# ConstantCurrentTester.net
KiCad netlist of a schematic drawn in EAGLE
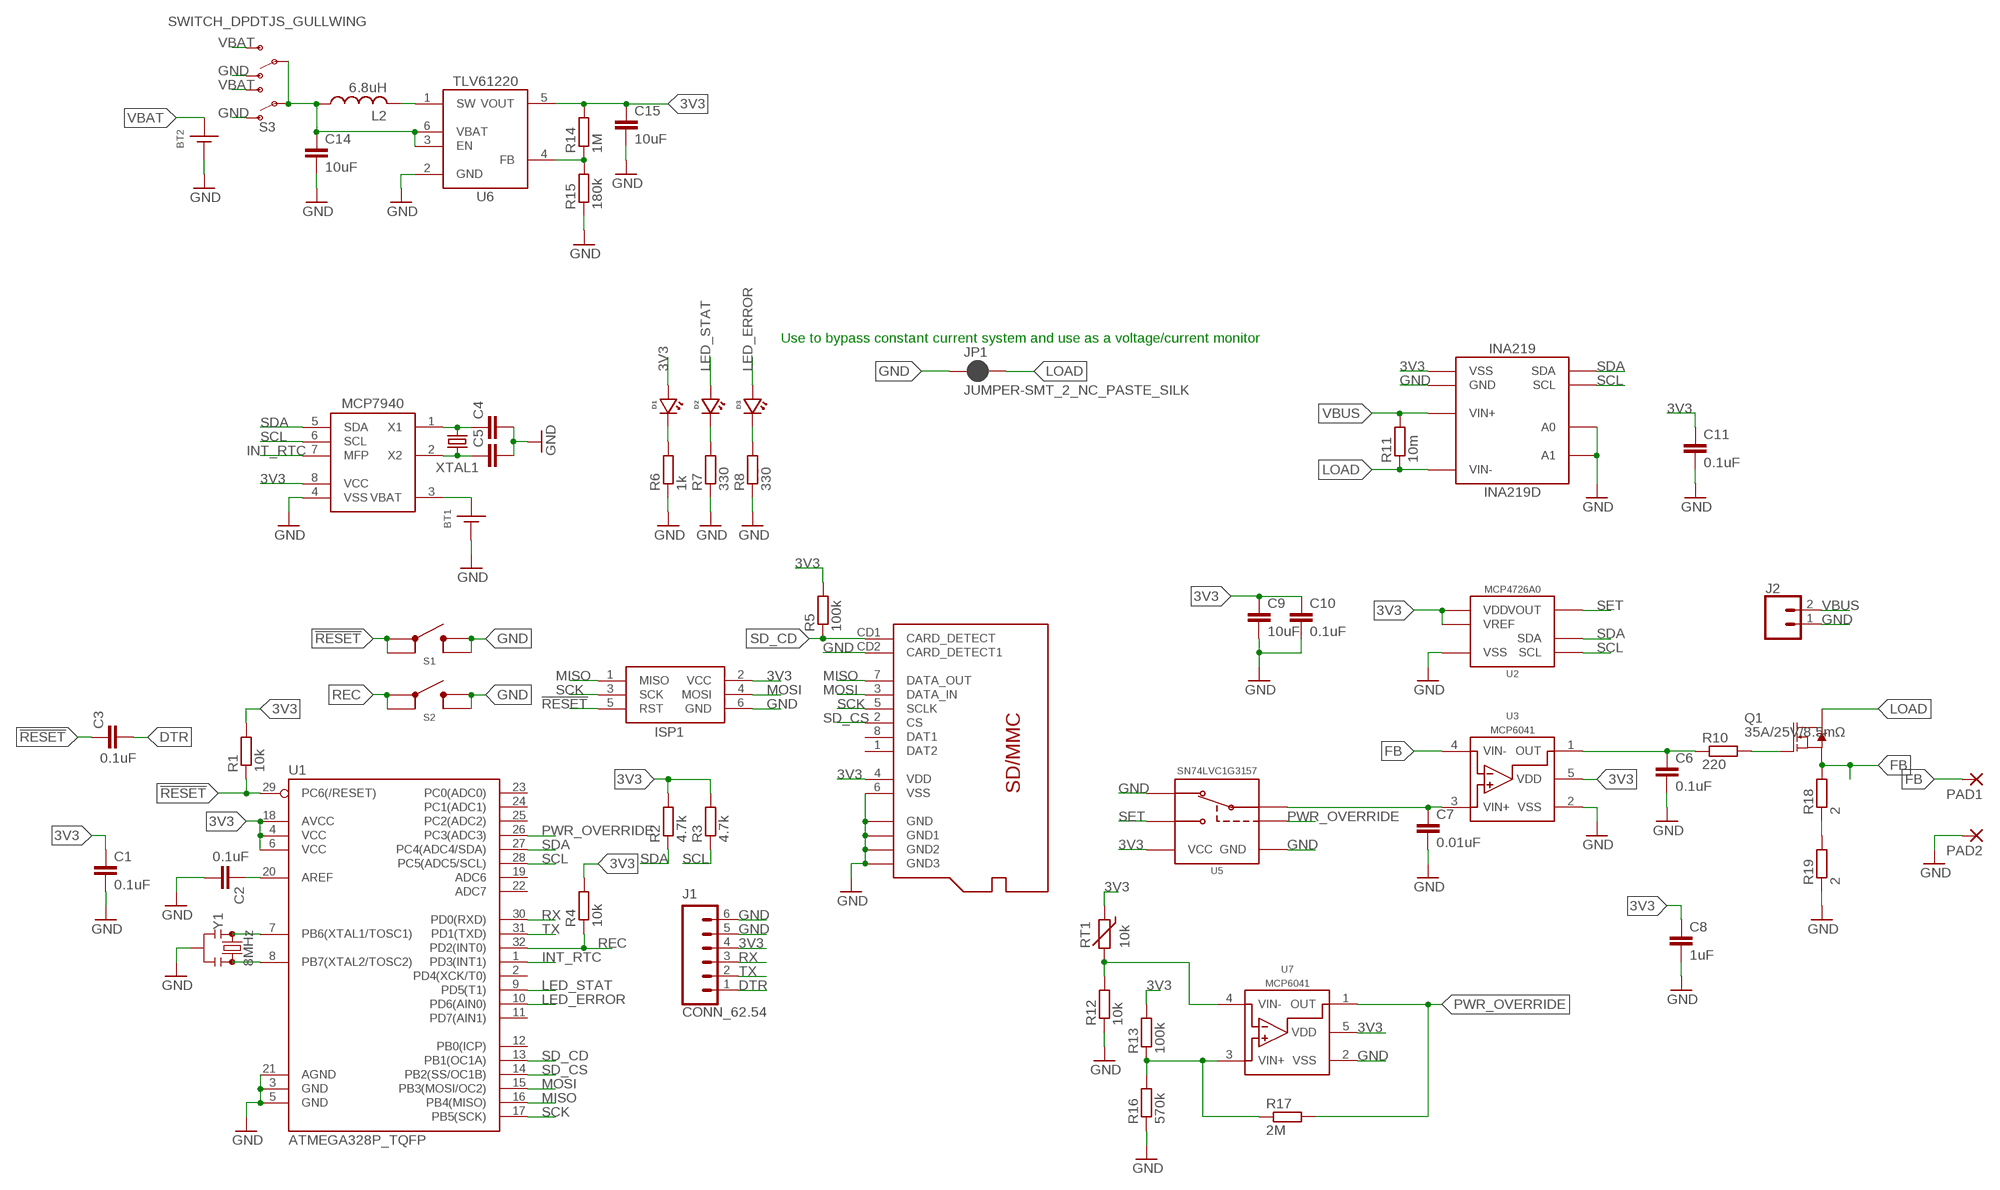
[diagram p0: schematic, sheet 1]

(export (version "E")
  (design (tool "Eeschema 10.0.6"))
  (components
    (comp (ref "BT1")
      (value "BATTERY_COIN12MM")
      (footprint "eagle-import:LINX_BAT-HLD-012-SMT")
      (fields (field (name "MF") "Linx") (field (name "MPN") "BAT-HLD-012-SMT"))
      (libsource (lib "eagle-import") (part "BATTERY_COIN12MM"))
    )
    (comp (ref "BT2")
      (value "BATTERY_COINAA")
      (footprint "eagle-import:BK-53")
      (libsource (lib "eagle-import") (part "BATTERY_COINAA"))
    )
    (comp (ref "C1")
      (value "0.1uF")
      (footprint "eagle-import:C0603")
      (fields (field (name "MF") "Murata") (field (name "MPN") "GCM188R71E104KA57D"))
      (libsource (lib "eagle-import") (part "C-EUC06030.1UF"))
    )
    (comp (ref "C2")
      (value "0.1uF")
      (footprint "eagle-import:C0603")
      (fields (field (name "MF") "Murata") (field (name "MPN") "GCM188R71E104KA57D"))
      (libsource (lib "eagle-import") (part "C-EUC06030.1UF"))
    )
    (comp (ref "C3")
      (value "0.1uF")
      (footprint "eagle-import:C0603")
      (fields (field (name "MF") "Murata") (field (name "MPN") "GCM188R71E104KA57D"))
      (libsource (lib "eagle-import") (part "C-EUC06030.1UF"))
    )
    (comp (ref "C4")
      (value "C-EUC0603")
      (footprint "eagle-import:C0603")
      (libsource (lib "eagle-import") (part "C-EUC0603"))
    )
    (comp (ref "C5")
      (value "C-EUC0603")
      (footprint "eagle-import:C0603")
      (libsource (lib "eagle-import") (part "C-EUC0603"))
    )
    (comp (ref "C6")
      (value "0.1uF")
      (footprint "eagle-import:C0603")
      (fields (field (name "MF") "Murata") (field (name "MPN") "GCM188R71E104KA57D"))
      (libsource (lib "eagle-import") (part "C-EUC06030.1UF"))
    )
    (comp (ref "C7")
      (value "0.01uF")
      (footprint "eagle-import:C0603")
      (libsource (lib "eagle-import") (part "C-EUC0603"))
    )
    (comp (ref "C8")
      (value "1uF")
      (footprint "eagle-import:C0603")
      (fields (field (name "MF") "Yaiyo Yuden") (field (name "MPN") "EMK107BJ105KA-T"))
      (libsource (lib "eagle-import") (part "C-EUC06031UF"))
    )
    (comp (ref "C9")
      (value "10uF")
      (footprint "eagle-import:C0805")
      (fields (field (name "MF") "Murata") (field (name "MPN") "GRM21BR61C106KE15K"))
      (libsource (lib "eagle-import") (part "C-EUC080510UF"))
    )
    (comp (ref "C10")
      (value "0.1uF")
      (footprint "eagle-import:C0603")
      (fields (field (name "MF") "Murata") (field (name "MPN") "GCM188R71E104KA57D"))
      (libsource (lib "eagle-import") (part "C-EUC06030.1UF"))
    )
    (comp (ref "C11")
      (value "0.1uF")
      (footprint "eagle-import:C0603")
      (fields (field (name "MF") "Murata") (field (name "MPN") "GCM188R71E104KA57D"))
      (libsource (lib "eagle-import") (part "C-EUC06030.1UF"))
    )
    (comp (ref "C14")
      (value "10uF")
      (footprint "eagle-import:C0805")
      (fields (field (name "MF") "Murata") (field (name "MPN") "GRM21BR61C106KE15K"))
      (libsource (lib "eagle-import") (part "C-EUC080510UF"))
    )
    (comp (ref "C15")
      (value "10uF")
      (footprint "eagle-import:C0805")
      (fields (field (name "MF") "Murata") (field (name "MPN") "GRM21BR61C106KE15K"))
      (libsource (lib "eagle-import") (part "C-EUC080510UF"))
    )
    (comp (ref "D1")
      (value "LEDBLUE0603")
      (footprint "eagle-import:LED_0603")
      (fields (field (name "MF") "Wurth") (field (name "MPN") "150060BS75000"))
      (libsource (lib "eagle-import") (part "LED0603BLUE"))
    )
    (comp (ref "D2")
      (value "LEDGREEN0603")
      (footprint "eagle-import:LED_0603")
      (fields (field (name "MF") "Wurth") (field (name "MPN") "150060GS75000"))
      (libsource (lib "eagle-import") (part "LED0603GREEN"))
    )
    (comp (ref "D3")
      (value "LEDRED0603")
      (footprint "eagle-import:LED_0603")
      (fields (field (name "MF") "Wurth") (field (name "MPN") "150060RS75000"))
      (libsource (lib "eagle-import") (part "LED0603RED"))
    )
    (comp (ref "ISP1")
      (value "AVRISP-6")
      (footprint "eagle-import:AVRISP")
      (libsource (lib "eagle-import") (part "AVRISP-6"))
    )
    (comp (ref "J1")
      (value "CONN_62.54")
      (footprint "eagle-import:1X06")
      (libsource (lib "eagle-import") (part "CONN_62.54"))
    )
    (comp (ref "J2")
      (value "CONN_023.5MM")
      (footprint "eagle-import:SCREWTERMINAL-3.5MM-2")
      (fields (field (name "MF") "On Shore Technology") (field (name "MPN") "OSTTE020161"))
      (libsource (lib "eagle-import") (part "CONN_023.5MM"))
    )
    (comp (ref "JP1")
      (value "JUMPER-SMT_2_NC_PASTE_SILK")
      (footprint "eagle-import:SMT-JUMPER_2_NC_PASTE_SILK")
      (libsource (lib "eagle-import") (part "JUMPER-SMT_2_NC_PASTE_SILK"))
    )
    (comp (ref "L2")
      (value "6.8uH")
      (footprint "eagle-import:1008")
      (fields (field (name "MF") "Wurth") (field (name "MPN") "74438323068"))
      (libsource (lib "eagle-import") (part "INDUCTOR1008"))
    )
    (comp (ref "PAD1")
      (value "3,81/1,4")
      (footprint "eagle-import:3,81_1,4")
      (libsource (lib "eagle-import") (part "3,81/1,4"))
    )
    (comp (ref "PAD2")
      (value "3,81/1,4")
      (footprint "eagle-import:3,81_1,4")
      (libsource (lib "eagle-import") (part "3,81/1,4"))
    )
    (comp (ref "Q1")
      (value "35A/25V/8.5mΩ")
      (footprint "eagle-import:DPAK")
      (libsource (lib "eagle-import") (part "MOSFET-NCH-FDD8780"))
    )
    (comp (ref "R1")
      (value "10k")
      (footprint "eagle-import:R0603")
      (fields (field (name "MF") "Yageo") (field (name "MPN") "RC0603FR-0710KL"))
      (libsource (lib "eagle-import") (part "R-EU_R060310K"))
    )
    (comp (ref "R2")
      (value "4.7k")
      (footprint "eagle-import:R0603")
      (fields (field (name "MF") "Yageo") (field (name "MPN") "RC0603FR-074K7L"))
      (libsource (lib "eagle-import") (part "R-EU_R06034.7K"))
    )
    (comp (ref "R3")
      (value "4.7k")
      (footprint "eagle-import:R0603")
      (fields (field (name "MF") "Yageo") (field (name "MPN") "RC0603FR-074K7L"))
      (libsource (lib "eagle-import") (part "R-EU_R06034.7K"))
    )
    (comp (ref "R4")
      (value "10k")
      (footprint "eagle-import:R0603")
      (fields (field (name "MF") "Yageo") (field (name "MPN") "RC0603FR-0710KL"))
      (libsource (lib "eagle-import") (part "R-EU_R060310K"))
    )
    (comp (ref "R5")
      (value "100k")
      (footprint "eagle-import:R0603")
      (fields (field (name "MF") "Yageo") (field (name "MPN") "RC0603FR-07100KL"))
      (libsource (lib "eagle-import") (part "R-EU_R0603100K"))
    )
    (comp (ref "R6")
      (value "1k")
      (footprint "eagle-import:R0603")
      (fields (field (name "MF") "Yageo") (field (name "MPN") "AC0603FR-071KL"))
      (libsource (lib "eagle-import") (part "R-EU_R06031K"))
    )
    (comp (ref "R7")
      (value "330")
      (footprint "eagle-import:R0603")
      (fields (field (name "MF") "Yageo") (field (name "MPN") "RC0603FR-07330RL"))
      (libsource (lib "eagle-import") (part "bschulz_passives_R-EU_R0603330"))
    )
    (comp (ref "R8")
      (value "330")
      (footprint "eagle-import:R0603")
      (fields (field (name "MF") "Yageo") (field (name "MPN") "RC0603FR-07330RL"))
      (libsource (lib "eagle-import") (part "bschulz_passives_R-EU_R0603330"))
    )
    (comp (ref "R10")
      (value "220")
      (footprint "eagle-import:R0603")
      (fields (field (name "MF") "Yageo") (field (name "MPN") "RC0603FR-07220RL"))
      (libsource (lib "eagle-import") (part "R-EU_R0603220"))
    )
    (comp (ref "R11")
      (value "10m")
      (footprint "eagle-import:R0805")
      (fields (field (name "MF") "Bourns") (field (name "MPN") "CRF0805-FZ-R010ELF"))
      (libsource (lib "eagle-import") (part "R-EU_R08050.01"))
    )
    (comp (ref "R12")
      (value "10k")
      (footprint "eagle-import:R0603")
      (fields (field (name "MF") "Yageo") (field (name "MPN") "RC0603FR-0710KL"))
      (libsource (lib "eagle-import") (part "bschulz_passives_R-EU_R060310K"))
    )
    (comp (ref "R13")
      (value "100k")
      (footprint "eagle-import:R0603")
      (fields (field (name "MF") "Yageo") (field (name "MPN") "RC0603FR-07100KL"))
      (libsource (lib "eagle-import") (part "R-EU_R0603100K"))
    )
    (comp (ref "R14")
      (value "1M")
      (footprint "eagle-import:R0603")
      (fields (field (name "MF") "Panasonic") (field (name "MPN") "ERJ-3EKF1004V"))
      (libsource (lib "eagle-import") (part "R-EU_R06031M"))
    )
    (comp (ref "R15")
      (value "180k")
      (footprint "eagle-import:R0603")
      (fields (field (name "MF") "Panasonic") (field (name "MPN") "ERJ-3EKF1803V"))
      (libsource (lib "eagle-import") (part "R-EU_R0603180K"))
    )
    (comp (ref "R16")
      (value "570k")
      (footprint "eagle-import:R0603")
      (fields (field (name "MF") "Yageo"))
      (libsource (lib "eagle-import") (part "bschulz_passives_R-EU_R0603"))
    )
    (comp (ref "R17")
      (value "2M")
      (footprint "eagle-import:R0603")
      (fields (field (name "MF") "Yageo"))
      (libsource (lib "eagle-import") (part "bschulz_passives_R-EU_R0603"))
    )
    (comp (ref "R18")
      (value "2")
      (footprint "eagle-import:R2512")
      (libsource (lib "eagle-import") (part "bschulz_passives_R-EU_R2512"))
    )
    (comp (ref "R19")
      (value "2")
      (footprint "eagle-import:R2512")
      (libsource (lib "eagle-import") (part "bschulz_passives_R-EU_R2512"))
    )
    (comp (ref "RT1")
      (value "10k")
      (footprint "eagle-import:R0603")
      (fields
        (field (name "MF") "Murata")
        (field (name "MPN") "NCU18XH103F60RB")
        (field (name "DIGIKEY") "P12011CT-ND")
        (field (name "MF_1") "Panasonic")
        (field (name "MPN_1") "ERT-J1VG103FA")
      )
      (libsource (lib "eagle-import") (part "THERMISTOR10K"))
    )
    (comp (ref "S1")
      (value "BUTTON6X6_TH")
      (footprint "eagle-import:SWITCH_6MM_TH")
      (fields (field (name "MF") "TE Connectivity") (field (name "MPN") "1825910-6"))
      (libsource (lib "eagle-import") (part "BUTTON6X6_TH"))
    )
    (comp (ref "S2")
      (value "BUTTON6X6_TH")
      (footprint "eagle-import:SWITCH_6MM_TH")
      (fields (field (name "MF") "TE Connectivity") (field (name "MPN") "1825910-6"))
      (libsource (lib "eagle-import") (part "BUTTON6X6_TH"))
    )
    (comp (ref "S3")
      (value "SWITCH_DPDTJS_GULLWING")
      (footprint "eagle-import:JS202011SCQN")
      (fields (field (name "MF") "C&K") (field (name "MPN") "JS202011SCQN"))
      (libsource (lib "eagle-import") (part "SWITCH_DPDTJS_GULLWING"))
    )
    (comp (ref "U$1")
      (value "MICRO_SD")
      (footprint "eagle-import:CUSTOM-PARTS_SD_MICRO")
      (libsource (lib "eagle-import") (part "MICRO_SD"))
    )
    (comp (ref "U$2")
      (value "MCP7940SOIC")
      (footprint "eagle-import:SO08")
      (fields (field (name "MF") "Microchip") (field (name "MPN") "MCP7940N-I/SN"))
      (libsource (lib "eagle-import") (part "MCP7940SOIC"))
    )
    (comp (ref "U1")
      (value "ATMEGA328P_TQFP")
      (footprint "eagle-import:TQFP32-08")
      (fields (field (name "MF") "Atmel") (field (name "MPN") "ATMEGA328PB-AUR"))
      (libsource (lib "eagle-import") (part "ATMEGA328PTQFP_32"))
    )
    (comp (ref "U2")
      (value "MCP4726A0SOT-23")
      (footprint "eagle-import:SOT23-6L")
      (fields
        (field (name "DISP") "MCP4726A0")
        (field (name "MF") "Microchip")
        (field (name "MPN") "MCP4726A0T-E/CH")
      )
      (libsource (lib "eagle-import") (part "MCP4726SOT-23A0"))
    )
    (comp (ref "U3")
      (value "MCP6041")
      (footprint "eagle-import:SOT23-5")
      (fields
        (field (name "DISP") "MCP6041")
        (field (name "MF") "Microchip")
        (field (name "MPN") "MCP6041T-I/OT")
      )
      (libsource (lib "eagle-import") (part "MCP6041"))
    )
    (comp (ref "U4")
      (value "INA219D")
      (footprint "eagle-import:SOIC_8")
      (fields (field (name "MF") "TI") (field (name "MPN") "INA219AIDR"))
      (libsource (lib "eagle-import") (part "INA219D"))
    )
    (comp (ref "U5")
      (value "SN74LVC1G3157SC70")
      (footprint "eagle-import:DCK_R-PDSO-G6")
      (fields
        (field (name "DISP") "SN74LVC1G3157")
        (field (name "MF") "TI")
        (field (name "MPN") "SN74LVC1G3157DCKR")
      )
      (libsource (lib "eagle-import") (part "SN74LVC1G3157SC70"))
    )
    (comp (ref "U6")
      (value "TLV61220DBV")
      (footprint "eagle-import:DBV_R-PDSO-G6")
      (fields (field (name "MF") "TI") (field (name "MPN") "TLV61220DBVR"))
      (libsource (lib "eagle-import") (part "TLV61220DBV"))
    )
    (comp (ref "U7")
      (value "MCP6041")
      (footprint "eagle-import:SOT23-5")
      (fields
        (field (name "DISP") "MCP6041")
        (field (name "MF") "Microchip")
        (field (name "MPN") "MCP6041T-I/OT")
      )
      (libsource (lib "eagle-import") (part "MCP6041"))
    )
    (comp (ref "XTAL1")
      (value "CRYSTAL3.2X1.5")
      (footprint "eagle-import:CRYSTAL_3.2X1.5_2-SMD")
      (libsource (lib "eagle-import") (part "CRYSTAL3.2X1.5"))
    )
    (comp (ref "Y1")
      (value "8MHz")
      (footprint "eagle-import:RESONATOR-SMD-3.2X1.3")
      (fields (field (name "MF") "Murata") (field (name "MPN") "CSTNE8M00G55Z000R0"))
      (libsource (lib "eagle-import") (part "RESONATORSMD_3.2X1.38MHZ"))
    )
  )
  (nets
    (net (code "1") (name "/INT_RTC") (class "Default")
      (node (ref "U$2") (pin "7") (pinfunction "MFP_7") (pintype "bidirectional"))
      (node (ref "U1") (pin "1") (pinfunction "PD3(INT1)_1") (pintype "bidirectional"))
    )
    (net (code "2") (name "/LED_ERROR") (class "Default")
      (node (ref "D3") (pin "ANODE") (pinfunction "ANODE_ANODE") (pintype "power_in"))
      (node (ref "U1") (pin "10") (pinfunction "PD6(AIN0)_10") (pintype "bidirectional"))
    )
    (net (code "3") (name "/LED_STAT") (class "Default")
      (node (ref "D2") (pin "ANODE") (pinfunction "ANODE_ANODE") (pintype "power_in"))
      (node (ref "U1") (pin "9") (pinfunction "PD5(T1)_9") (pintype "bidirectional"))
    )
    (net (code "4") (name "/MISO") (class "Default")
      (node (ref "ISP1") (pin "1") (pinfunction "MISO_1") (pintype "input"))
      (node (ref "U$1") (pin "7") (pinfunction "DATA_OUT_7") (pintype "bidirectional"))
      (node (ref "U1") (pin "16") (pinfunction "PB4(MISO)_16") (pintype "bidirectional"))
    )
    (net (code "5") (name "/MOSI") (class "Default")
      (node (ref "ISP1") (pin "4") (pinfunction "MOSI_4") (pintype "output"))
      (node (ref "U$1") (pin "3") (pinfunction "DATA_IN_3") (pintype "bidirectional"))
      (node (ref "U1") (pin "15") (pinfunction "PB3(MOSI/OC2)_15") (pintype "bidirectional"))
    )
    (net (code "6") (name "/RX") (class "Default")
      (node (ref "J1") (pin "3") (pinfunction "3_3") (pintype "passive"))
      (node (ref "U1") (pin "30") (pinfunction "PD0(RXD)_30") (pintype "bidirectional"))
    )
    (net (code "7") (name "/SCK") (class "Default")
      (node (ref "ISP1") (pin "3") (pinfunction "SCK_3") (pintype "output"))
      (node (ref "U$1") (pin "5") (pinfunction "SCLK_5") (pintype "bidirectional"))
      (node (ref "U1") (pin "17") (pinfunction "PB5(SCK)_17") (pintype "bidirectional"))
    )
    (net (code "8") (name "/SCL") (class "Default")
      (node (ref "R3") (pin "1") (pinfunction "1_1") (pintype "passive"))
      (node (ref "U$2") (pin "6") (pinfunction "SCL_6") (pintype "bidirectional"))
      (node (ref "U1") (pin "28") (pinfunction "PC5(ADC5/SCL)_28") (pintype "bidirectional"))
      (node (ref "U2") (pin "5") (pinfunction "SCL_5") (pintype "bidirectional"))
      (node (ref "U4") (pin "4") (pinfunction "SCL_4") (pintype "input"))
    )
    (net (code "9") (name "/SDA") (class "Default")
      (node (ref "R2") (pin "1") (pinfunction "1_1") (pintype "passive"))
      (node (ref "U$2") (pin "5") (pinfunction "SDA_5") (pintype "bidirectional"))
      (node (ref "U1") (pin "27") (pinfunction "PC4(ADC4/SDA)_27") (pintype "bidirectional"))
      (node (ref "U2") (pin "4") (pinfunction "SDA_4") (pintype "bidirectional"))
      (node (ref "U4") (pin "3") (pinfunction "SDA_3") (pintype "bidirectional"))
    )
    (net (code "10") (name "/SD_CS") (class "Default")
      (node (ref "U$1") (pin "2") (pinfunction "CS_2") (pintype "bidirectional"))
      (node (ref "U1") (pin "14") (pinfunction "PB2(SS/OC1B)_14") (pintype "bidirectional"))
    )
    (net (code "11") (name "/SET") (class "Default")
      (node (ref "C7") (pin "1") (pinfunction "1_1") (pintype "passive"))
      (node (ref "U2") (pin "1") (pinfunction "VOUT_1") (pintype "output"))
      (node (ref "U3") (pin "3") (pinfunction "VIN+_3") (pintype "input"))
      (node (ref "U5") (pin "1") (pinfunction "B2_1") (pintype "bidirectional"))
      (node (ref "U5") (pin "4") (pinfunction "A_4") (pintype "bidirectional"))
    )
    (net (code "12") (name "/TX") (class "Default")
      (node (ref "J1") (pin "2") (pinfunction "2_2") (pintype "passive"))
      (node (ref "U1") (pin "31") (pinfunction "PD1(TXD)_31") (pintype "bidirectional"))
    )
    (net (code "13") (name "/~{RESET}") (class "Default")
      (node (ref "C3") (pin "1") (pinfunction "1_1") (pintype "passive"))
      (node (ref "ISP1") (pin "5") (pinfunction "RST_5") (pintype "output"))
      (node (ref "R1") (pin "1") (pinfunction "1_1") (pintype "passive"))
      (node (ref "S1") (pin "1") (pinfunction "1_1") (pintype "bidirectional"))
      (node (ref "S1") (pin "2") (pinfunction "2_2") (pintype "bidirectional"))
      (node (ref "U1") (pin "29") (pinfunction "PC6(/RESET)_29") (pintype "bidirectional"))
    )
    (net (code "14") (name "3V3") (class "Default")
      (node (ref "C1") (pin "1") (pinfunction "1_1") (pintype "passive"))
      (node (ref "C10") (pin "1") (pinfunction "1_1") (pintype "passive"))
      (node (ref "C11") (pin "1") (pinfunction "1_1") (pintype "passive"))
      (node (ref "C15") (pin "1") (pinfunction "1_1") (pintype "passive"))
      (node (ref "C8") (pin "1") (pinfunction "1_1") (pintype "passive"))
      (node (ref "C9") (pin "1") (pinfunction "1_1") (pintype "passive"))
      (node (ref "D1") (pin "ANODE") (pinfunction "ANODE_ANODE") (pintype "power_in"))
      (node (ref "ISP1") (pin "2") (pinfunction "VCC_2") (pintype "power_in"))
      (node (ref "J1") (pin "4") (pinfunction "4_4") (pintype "passive"))
      (node (ref "R1") (pin "2") (pinfunction "2_2") (pintype "passive"))
      (node (ref "R13") (pin "2") (pinfunction "2_2") (pintype "passive"))
      (node (ref "R14") (pin "2") (pinfunction "2_2") (pintype "passive"))
      (node (ref "R2") (pin "2") (pinfunction "2_2") (pintype "passive"))
      (node (ref "R3") (pin "2") (pinfunction "2_2") (pintype "passive"))
      (node (ref "R4") (pin "2") (pinfunction "2_2") (pintype "passive"))
      (node (ref "R5") (pin "2") (pinfunction "2_2") (pintype "passive"))
      (node (ref "RT1") (pin "1") (pinfunction "2_1") (pintype "passive"))
      (node (ref "U$1") (pin "4") (pinfunction "VDD_4") (pintype "bidirectional"))
      (node (ref "U$2") (pin "8") (pinfunction "VCC_8") (pintype "bidirectional"))
      (node (ref "U1") (pin "18") (pinfunction "AVCC_18") (pintype "bidirectional"))
      (node (ref "U1") (pin "4") (pinfunction "VCC_4") (pintype "bidirectional"))
      (node (ref "U1") (pin "6") (pinfunction "VCC_6") (pintype "bidirectional"))
      (node (ref "U2") (pin "3") (pinfunction "VDD_3") (pintype "power_in"))
      (node (ref "U2") (pin "6") (pinfunction "VREF_6") (pintype "power_in"))
      (node (ref "U3") (pin "5") (pinfunction "VDD_5") (pintype "power_in"))
      (node (ref "U4") (pin "5") (pinfunction "VSS_5") (pintype "power_in"))
      (node (ref "U5") (pin "5") (pinfunction "VCC_5") (pintype "power_in"))
      (node (ref "U6") (pin "5") (pinfunction "VOUT_5") (pintype "power_in"))
      (node (ref "U7") (pin "5") (pinfunction "VDD_5") (pintype "power_in"))
    )
    (net (code "15") (name "DTR") (class "Default")
      (node (ref "C3") (pin "2") (pinfunction "2_2") (pintype "passive"))
      (node (ref "J1") (pin "1") (pinfunction "1_1") (pintype "passive"))
    )
    (net (code "16") (name "FB") (class "Default")
      (node (ref "PAD1") (pin "1") (pinfunction "P_1") (pintype "passive"))
      (node (ref "Q1") (pin "3") (pinfunction "S_3") (pintype "bidirectional"))
      (node (ref "R18") (pin "2") (pinfunction "2_2") (pintype "passive"))
      (node (ref "U3") (pin "4") (pinfunction "VIN-_4") (pintype "input"))
    )
    (net (code "17") (name "GND") (class "Default")
      (node (ref "BT1") (pin "GND") (pinfunction "-_GND") (pintype "bidirectional"))
      (node (ref "BT2") (pin "NEG@1") (pinfunction "-_NEG@1") (pintype "bidirectional"))
      (node (ref "BT2") (pin "NEG@2") (pinfunction "-_NEG@2") (pintype "bidirectional"))
      (node (ref "C1") (pin "2") (pinfunction "2_2") (pintype "passive"))
      (node (ref "C10") (pin "2") (pinfunction "2_2") (pintype "passive"))
      (node (ref "C11") (pin "2") (pinfunction "2_2") (pintype "passive"))
      (node (ref "C14") (pin "2") (pinfunction "2_2") (pintype "passive"))
      (node (ref "C15") (pin "2") (pinfunction "2_2") (pintype "passive"))
      (node (ref "C2") (pin "2") (pinfunction "2_2") (pintype "passive"))
      (node (ref "C4") (pin "2") (pinfunction "2_2") (pintype "passive"))
      (node (ref "C5") (pin "2") (pinfunction "2_2") (pintype "passive"))
      (node (ref "C6") (pin "2") (pinfunction "2_2") (pintype "passive"))
      (node (ref "C7") (pin "2") (pinfunction "2_2") (pintype "passive"))
      (node (ref "C8") (pin "2") (pinfunction "2_2") (pintype "passive"))
      (node (ref "C9") (pin "2") (pinfunction "2_2") (pintype "passive"))
      (node (ref "ISP1") (pin "6") (pinfunction "GND_6") (pintype "power_in"))
      (node (ref "J1") (pin "5") (pinfunction "5_5") (pintype "passive"))
      (node (ref "J1") (pin "6") (pinfunction "6_6") (pintype "passive"))
      (node (ref "J2") (pin "1") (pinfunction "1_1") (pintype "passive"))
      (node (ref "JP1") (pin "1") (pinfunction "1_1") (pintype "passive"))
      (node (ref "PAD2") (pin "1") (pinfunction "P_1") (pintype "passive"))
      (node (ref "R12") (pin "1") (pinfunction "1_1") (pintype "passive"))
      (node (ref "R15") (pin "1") (pinfunction "1_1") (pintype "passive"))
      (node (ref "R16") (pin "1") (pinfunction "1_1") (pintype "passive"))
      (node (ref "R19") (pin "1") (pinfunction "1_1") (pintype "passive"))
      (node (ref "R6") (pin "1") (pinfunction "1_1") (pintype "passive"))
      (node (ref "R7") (pin "1") (pinfunction "1_1") (pintype "passive"))
      (node (ref "R8") (pin "1") (pinfunction "1_1") (pintype "passive"))
      (node (ref "S1") (pin "3") (pinfunction "3_3") (pintype "bidirectional"))
      (node (ref "S1") (pin "4") (pinfunction "4_4") (pintype "bidirectional"))
      (node (ref "S2") (pin "3") (pinfunction "3_3") (pintype "bidirectional"))
      (node (ref "S2") (pin "4") (pinfunction "4_4") (pintype "bidirectional"))
      (node (ref "S3") (pin "1") (pinfunction "O1_1") (pintype "passive"))
      (node (ref "S3") (pin "6") (pinfunction "O2_6") (pintype "passive"))
      (node (ref "U$1") (pin "6") (pinfunction "VSS_6") (pintype "bidirectional"))
      (node (ref "U$1") (pin "CD2") (pinfunction "CARD_DETECT1_CD2") (pintype "bidirectional"))
      (node (ref "U$1") (pin "GND@1") (pinfunction "GND_GND@1") (pintype "bidirectional"))
      (node (ref "U$1") (pin "GND@2") (pinfunction "GND1_GND@2") (pintype "bidirectional"))
      (node (ref "U$1") (pin "GND@3") (pinfunction "GND2_GND@3") (pintype "bidirectional"))
      (node (ref "U$1") (pin "GND@5") (pinfunction "GND3_GND@5") (pintype "bidirectional"))
      (node (ref "U$2") (pin "4") (pinfunction "VSS_4") (pintype "bidirectional"))
      (node (ref "U1") (pin "21") (pinfunction "AGND_21") (pintype "bidirectional"))
      (node (ref "U1") (pin "3") (pinfunction "GND_3") (pintype "bidirectional"))
      (node (ref "U1") (pin "5") (pinfunction "GND_5") (pintype "bidirectional"))
      (node (ref "U2") (pin "2") (pinfunction "VSS_2") (pintype "power_in"))
      (node (ref "U3") (pin "2") (pinfunction "VSS_2") (pintype "power_in"))
      (node (ref "U4") (pin "1") (pinfunction "A1_1") (pintype "input"))
      (node (ref "U4") (pin "2") (pinfunction "A0_2") (pintype "input"))
      (node (ref "U4") (pin "6") (pinfunction "GND_6") (pintype "power_in"))
      (node (ref "U5") (pin "2") (pinfunction "GND_2") (pintype "power_in"))
      (node (ref "U5") (pin "3") (pinfunction "B1_3") (pintype "bidirectional"))
      (node (ref "U6") (pin "2") (pinfunction "GND_2") (pintype "power_in"))
      (node (ref "U7") (pin "2") (pinfunction "VSS_2") (pintype "power_in"))
      (node (ref "Y1") (pin "2") (pinfunction "2_2") (pintype "passive"))
    )
    (net (code "18") (name "LOAD") (class "Default")
      (node (ref "JP1") (pin "2") (pinfunction "2_2") (pintype "passive"))
      (node (ref "Q1") (pin "4") (pinfunction "D_4") (pintype "bidirectional"))
      (node (ref "R11") (pin "1") (pinfunction "1_1") (pintype "passive"))
      (node (ref "U4") (pin "7") (pinfunction "VIN-_7") (pintype "input"))
    )
    (net (code "19") (name "Net-(D1-PadCATHODE)") (class "Default")
      (node (ref "D1") (pin "CATHODE") (pinfunction "CATHODE_CATHODE") (pintype "power_in"))
      (node (ref "R6") (pin "2") (pinfunction "2_2") (pintype "passive"))
    )
    (net (code "20") (name "Net-(D2-PadCATHODE)") (class "Default")
      (node (ref "D2") (pin "CATHODE") (pinfunction "CATHODE_CATHODE") (pintype "power_in"))
      (node (ref "R7") (pin "2") (pinfunction "2_2") (pintype "passive"))
    )
    (net (code "21") (name "Net-(D3-PadCATHODE)") (class "Default")
      (node (ref "D3") (pin "CATHODE") (pinfunction "CATHODE_CATHODE") (pintype "power_in"))
      (node (ref "R8") (pin "2") (pinfunction "2_2") (pintype "passive"))
    )
    (net (code "22") (name "Net-(Q1-G)") (class "Default")
      (node (ref "Q1") (pin "1") (pinfunction "G_1") (pintype "bidirectional"))
      (node (ref "R10") (pin "2") (pinfunction "2_2") (pintype "passive"))
    )
    (net (code "23") (name "Net-(R18-Pad1)") (class "Default")
      (node (ref "R18") (pin "1") (pinfunction "1_1") (pintype "passive"))
      (node (ref "R19") (pin "2") (pinfunction "2_2") (pintype "passive"))
    )
    (net (code "24") (name "Net-(RT1-1)") (class "Default")
      (node (ref "R12") (pin "2") (pinfunction "2_2") (pintype "passive"))
      (node (ref "RT1") (pin "2") (pinfunction "1_2") (pintype "passive"))
      (node (ref "U7") (pin "4") (pinfunction "VIN-_4") (pintype "input"))
    )
    (net (code "25") (name "Net-(S3-P1)") (class "Default")
      (node (ref "C14") (pin "1") (pinfunction "1_1") (pintype "passive"))
      (node (ref "L2") (pin "1") (pinfunction "1_1") (pintype "passive"))
      (node (ref "S3") (pin "2") (pinfunction "P1_2") (pintype "passive"))
      (node (ref "S3") (pin "5") (pinfunction "P2_5") (pintype "passive"))
      (node (ref "U6") (pin "3") (pinfunction "EN_3") (pintype "input"))
      (node (ref "U6") (pin "6") (pinfunction "VBAT_6") (pintype "power_in"))
    )
    (net (code "26") (name "Net-(U$2-VBAT)") (class "Default")
      (node (ref "BT1") (pin "POWER0") (pinfunction "+_POWER0") (pintype "bidirectional"))
      (node (ref "BT1") (pin "POWER1") (pinfunction "+_POWER1") (pintype "bidirectional"))
      (node (ref "U$2") (pin "3") (pinfunction "VBAT_3") (pintype "bidirectional"))
    )
    (net (code "27") (name "Net-(U$2-X1)") (class "Default")
      (node (ref "C4") (pin "1") (pinfunction "1_1") (pintype "passive"))
      (node (ref "U$2") (pin "1") (pinfunction "X1_1") (pintype "bidirectional"))
      (node (ref "XTAL1") (pin "P$1") (pinfunction "1_P$1") (pintype "passive"))
    )
    (net (code "28") (name "Net-(U$2-X2)") (class "Default")
      (node (ref "C5") (pin "1") (pinfunction "1_1") (pintype "passive"))
      (node (ref "U$2") (pin "2") (pinfunction "X2_2") (pintype "bidirectional"))
      (node (ref "XTAL1") (pin "P$2") (pinfunction "2_P$2") (pintype "passive"))
    )
    (net (code "29") (name "Net-(U1-AREF)") (class "Default")
      (node (ref "C2") (pin "1") (pinfunction "1_1") (pintype "passive"))
      (node (ref "U1") (pin "20") (pinfunction "AREF_20") (pintype "bidirectional"))
    )
    (net (code "30") (name "Net-(U1-PB6(XTAL1{slash}TOSC1))") (class "Default")
      (node (ref "U1") (pin "7") (pinfunction "PB6(XTAL1/TOSC1)_7") (pintype "bidirectional"))
      (node (ref "Y1") (pin "1") (pinfunction "1_1") (pintype "passive"))
    )
    (net (code "31") (name "Net-(U1-PB7(XTAL2{slash}TOSC2))") (class "Default")
      (node (ref "U1") (pin "8") (pinfunction "PB7(XTAL2/TOSC2)_8") (pintype "bidirectional"))
      (node (ref "Y1") (pin "3") (pinfunction "3_3") (pintype "passive"))
    )
    (net (code "32") (name "Net-(U3-OUT)") (class "Default")
      (node (ref "C6") (pin "1") (pinfunction "1_1") (pintype "passive"))
      (node (ref "R10") (pin "1") (pinfunction "1_1") (pintype "passive"))
      (node (ref "U3") (pin "1") (pinfunction "OUT_1") (pintype "output"))
    )
    (net (code "33") (name "Net-(U6-FB)") (class "Default")
      (node (ref "R14") (pin "1") (pinfunction "1_1") (pintype "passive"))
      (node (ref "R15") (pin "2") (pinfunction "2_2") (pintype "passive"))
      (node (ref "U6") (pin "4") (pinfunction "FB_4") (pintype "input"))
    )
    (net (code "34") (name "Net-(U6-SW)") (class "Default")
      (node (ref "L2") (pin "2") (pinfunction "2_2") (pintype "passive"))
      (node (ref "U6") (pin "1") (pinfunction "SW_1") (pintype "power_in"))
    )
    (net (code "35") (name "Net-(U7-VIN+)") (class "Default")
      (node (ref "R13") (pin "1") (pinfunction "1_1") (pintype "passive"))
      (node (ref "R16") (pin "2") (pinfunction "2_2") (pintype "passive"))
      (node (ref "R17") (pin "1") (pinfunction "1_1") (pintype "passive"))
      (node (ref "U7") (pin "3") (pinfunction "VIN+_3") (pintype "input"))
    )
    (net (code "36") (name "PWR_OVERRIDE") (class "Default")
      (node (ref "R17") (pin "2") (pinfunction "2_2") (pintype "passive"))
      (node (ref "U1") (pin "26") (pinfunction "PC3(ADC3)_26") (pintype "bidirectional"))
      (node (ref "U5") (pin "6") (pinfunction "S_6") (pintype "input"))
      (node (ref "U7") (pin "1") (pinfunction "OUT_1") (pintype "output"))
    )
    (net (code "37") (name "REC") (class "Default")
      (node (ref "R4") (pin "1") (pinfunction "1_1") (pintype "passive"))
      (node (ref "S2") (pin "1") (pinfunction "1_1") (pintype "bidirectional"))
      (node (ref "S2") (pin "2") (pinfunction "2_2") (pintype "bidirectional"))
      (node (ref "U1") (pin "32") (pinfunction "PD2(INT0)_32") (pintype "bidirectional"))
    )
    (net (code "38") (name "SD_CD") (class "Default")
      (node (ref "R5") (pin "1") (pinfunction "1_1") (pintype "passive"))
      (node (ref "U$1") (pin "CD1") (pinfunction "CARD_DETECT_CD1") (pintype "bidirectional"))
      (node (ref "U1") (pin "13") (pinfunction "PB1(OC1A)_13") (pintype "bidirectional"))
    )
    (net (code "39") (name "VBAT") (class "Default")
      (node (ref "BT2") (pin "POS@1") (pinfunction "+_POS@1") (pintype "bidirectional"))
      (node (ref "BT2") (pin "POS@2") (pinfunction "+_POS@2") (pintype "bidirectional"))
      (node (ref "S3") (pin "3") (pinfunction "S1_3") (pintype "passive"))
      (node (ref "S3") (pin "4") (pinfunction "S2_4") (pintype "passive"))
    )
    (net (code "40") (name "VBUS") (class "Default")
      (node (ref "J2") (pin "2") (pinfunction "2_2") (pintype "passive"))
      (node (ref "R11") (pin "2") (pinfunction "2_2") (pintype "passive"))
      (node (ref "U4") (pin "8") (pinfunction "VIN+_8") (pintype "input"))
    )
    (net (code "41") (name "unconnected-(U$1-DAT1-Pad8)") (class "Default")
      (node (ref "U$1") (pin "8") (pinfunction "DAT1_8") (pintype "bidirectional"))
    )
    (net (code "42") (name "unconnected-(U$1-DAT2-Pad1)") (class "Default")
      (node (ref "U$1") (pin "1") (pinfunction "DAT2_1") (pintype "bidirectional"))
    )
    (net (code "43") (name "unconnected-(U1-ADC6-Pad19)") (class "Default")
      (node (ref "U1") (pin "19") (pinfunction "ADC6_19") (pintype "bidirectional"))
    )
    (net (code "44") (name "unconnected-(U1-ADC7-Pad22)") (class "Default")
      (node (ref "U1") (pin "22") (pinfunction "ADC7_22") (pintype "bidirectional"))
    )
    (net (code "45") (name "unconnected-(U1-PB0(ICP)-Pad12)") (class "Default")
      (node (ref "U1") (pin "12") (pinfunction "PB0(ICP)_12") (pintype "bidirectional"))
    )
    (net (code "46") (name "unconnected-(U1-PC0(ADC0)-Pad23)") (class "Default")
      (node (ref "U1") (pin "23") (pinfunction "PC0(ADC0)_23") (pintype "bidirectional"))
    )
    (net (code "47") (name "unconnected-(U1-PC1(ADC1)-Pad24)") (class "Default")
      (node (ref "U1") (pin "24") (pinfunction "PC1(ADC1)_24") (pintype "bidirectional"))
    )
    (net (code "48") (name "unconnected-(U1-PC2(ADC2)-Pad25)") (class "Default")
      (node (ref "U1") (pin "25") (pinfunction "PC2(ADC2)_25") (pintype "bidirectional"))
    )
    (net (code "49") (name "unconnected-(U1-PD4(XCK{slash}T0)-Pad2)") (class "Default")
      (node (ref "U1") (pin "2") (pinfunction "PD4(XCK/T0)_2") (pintype "bidirectional"))
    )
    (net (code "50") (name "unconnected-(U1-PD7(AIN1)-Pad11)") (class "Default")
      (node (ref "U1") (pin "11") (pinfunction "PD7(AIN1)_11") (pintype "bidirectional"))
    )
  )
)
